# Skripsi_layout_v5.net
KiCad netlist of a schematic drawn in EAGLE
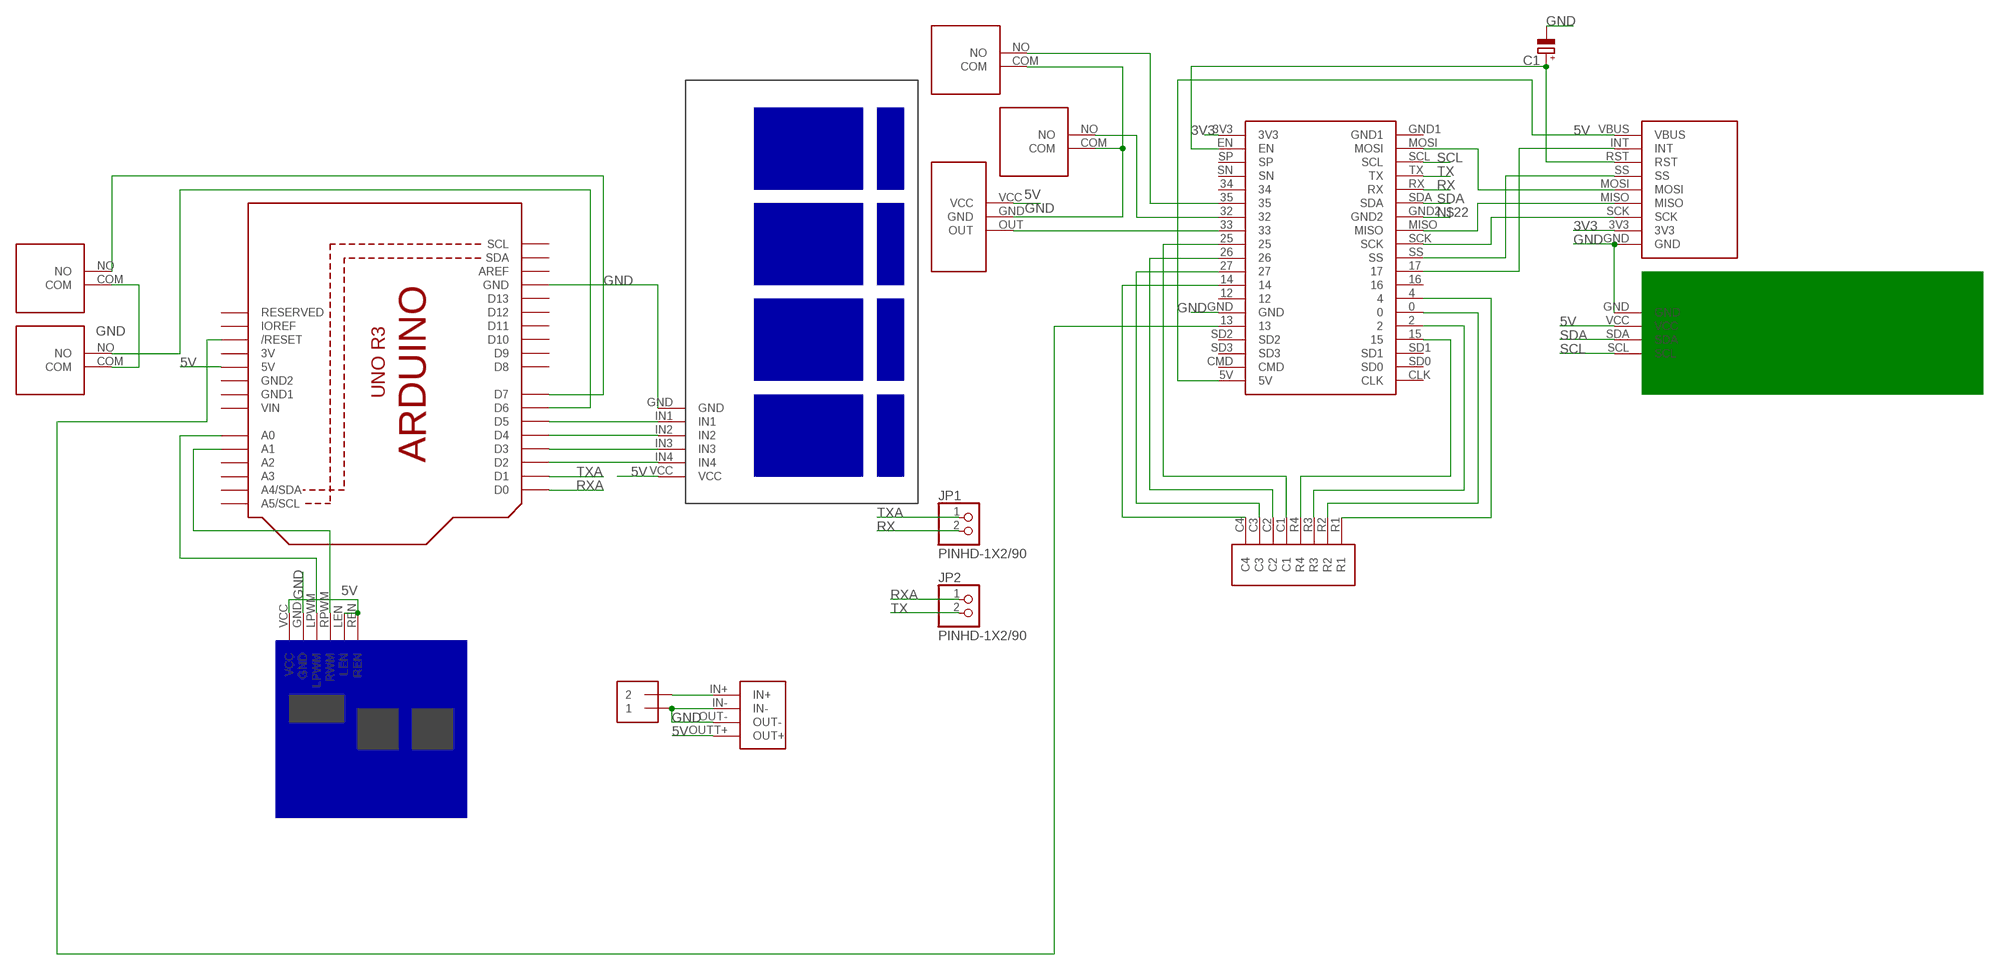
[diagram p0: schematic, sheet 1]

(export (version "E")
  (design (tool "Eeschema 10.0.6"))
  (components
    (comp (ref "C1")
      (value "C-POL_RADIAL-25MM-DIA")
      (footprint "eagle-import:CAPPRD550W110D1250H2500B")
      (libsource (lib "eagle-import") (part "C-POLRADIAL-25MM-DIA_"))
    )
    (comp (ref "J1")
      (value "1X2-3.5MM")
      (footprint "eagle-import:1X2-3.5MM")
      (libsource (lib "eagle-import") (part "1X2-3.5MM"))
    )
    (comp (ref "JP1")
      (value "PINHD-1X2/90")
      (footprint "eagle-import:1X02_90")
      (libsource (lib "eagle-import") (part "PINHD-1X2/90"))
    )
    (comp (ref "JP2")
      (value "PINHD-1X2/90")
      (footprint "eagle-import:1X02_90")
      (libsource (lib "eagle-import") (part "PINHD-1X2/90"))
    )
    (comp (ref "U$1")
      (value "ARDUINO_UNO")
      (footprint "eagle-import:ARDUINO_UNO")
      (libsource (lib "eagle-import") (part "ARDUINO_UNO"))
    )
    (comp (ref "U$2")
      (value "ESP32_NEW")
      (footprint "eagle-import:ESP32_NEW")
      (libsource (lib "eagle-import") (part "ESP32_NEW"))
    )
    (comp (ref "U$3")
      (value "USB_HOST")
      (footprint "eagle-import:USB_HOST")
      (libsource (lib "eagle-import") (part "USB_HOST"))
    )
    (comp (ref "U$4")
      (value "LCD_I2C")
      (footprint "eagle-import:LCD_I2C")
      (libsource (lib "eagle-import") (part "LCD_I2C"))
    )
    (comp (ref "U$5")
      (value "KEYPAD_4X4")
      (footprint "eagle-import:KEYPAD_4X4")
      (libsource (lib "eagle-import") (part "KEYPAD_4X4"))
    )
    (comp (ref "U$6")
      (value "IR_SENSOR")
      (footprint "eagle-import:IR_SENSOR")
      (libsource (lib "eagle-import") (part "IR_SENSOR"))
    )
    (comp (ref "U$7")
      (value "SWITCHLIMITER")
      (footprint "eagle-import:SWICHLIMITER")
      (libsource (lib "eagle-import") (part "SWITCHLIMITER"))
    )
    (comp (ref "U$8")
      (value "SWITCHLIMITER")
      (footprint "eagle-import:SWICHLIMITER")
      (libsource (lib "eagle-import") (part "SWITCHLIMITER"))
    )
    (comp (ref "U$9")
      (value "RELAY_4CHANNEL")
      (footprint "eagle-import:RELAY_4CHANNEL")
      (libsource (lib "eagle-import") (part "RELAY_4CHANNEL"))
    )
    (comp (ref "U$10")
      (value "MOTOR_DRIVER_BTS7960")
      (footprint "eagle-import:MOTOR_DRIVER_BTS7960")
      (libsource (lib "eagle-import") (part "MOTOR_DRIVER_BTS7960"))
    )
    (comp (ref "U$11")
      (value "SWITCHLIMITER")
      (footprint "eagle-import:SWICHLIMITER")
      (libsource (lib "eagle-import") (part "SWITCHLIMITER"))
    )
    (comp (ref "U$12")
      (value "SWITCHLIMITER")
      (footprint "eagle-import:SWICHLIMITER")
      (libsource (lib "eagle-import") (part "SWITCHLIMITER"))
    )
    (comp (ref "U$13")
      (value "XL4005E1")
      (footprint "eagle-import:XL4005E1")
      (libsource (lib "eagle-import") (part "XL4005E1"))
    )
  )
  (nets
    (net (code "1") (name "/3V") (class "Default")
      (node (ref "U$1") (pin "3V") (pinfunction "3V_3V") (pintype "power_in"))
    )
    (net (code "2") (name "/3V3") (class "Default")
      (node (ref "U$2") (pin "3V3") (pinfunction "3V3_3V3") (pintype "bidirectional"))
      (node (ref "U$3") (pin "3V3") (pinfunction "3V3_3V3") (pintype "bidirectional"))
    )
    (net (code "3") (name "/5V") (class "Default")
      (node (ref "U$1") (pin "5V") (pinfunction "5V_5V") (pintype "power_in"))
      (node (ref "U$10") (pin "LEN") (pinfunction "LEN_LEN") (pintype "bidirectional"))
      (node (ref "U$10") (pin "REN") (pinfunction "REN_REN") (pintype "bidirectional"))
      (node (ref "U$10") (pin "VCC") (pinfunction "VCC_VCC") (pintype "bidirectional"))
      (node (ref "U$13") (pin "OUTT+") (pinfunction "OUT+_OUTT+") (pintype "bidirectional"))
      (node (ref "U$2") (pin "5V") (pinfunction "5V_5V") (pintype "bidirectional"))
      (node (ref "U$3") (pin "VBUS") (pinfunction "VBUS_VBUS") (pintype "bidirectional"))
      (node (ref "U$4") (pin "VCC") (pinfunction "VCC_VCC") (pintype "bidirectional"))
      (node (ref "U$6") (pin "VCC") (pinfunction "VCC_VCC") (pintype "bidirectional"))
      (node (ref "U$9") (pin "VCC") (pinfunction "VCC_VCC") (pintype "bidirectional"))
    )
    (net (code "4") (name "/GND") (class "Default")
      (node (ref "C1") (pin "2") (pinfunction "-_2") (pintype "passive"))
      (node (ref "J1") (pin "1") (pinfunction "1_1") (pintype "passive"))
      (node (ref "U$1") (pin "GND") (pinfunction "GND_GND") (pintype "power_in"))
      (node (ref "U$10") (pin "GND") (pinfunction "GND_GND") (pintype "bidirectional"))
      (node (ref "U$11") (pin "COM") (pinfunction "COM_COM") (pintype "bidirectional"))
      (node (ref "U$12") (pin "COM") (pinfunction "COM_COM") (pintype "bidirectional"))
      (node (ref "U$13") (pin "IN-") (pinfunction "IN-_IN-") (pintype "bidirectional"))
      (node (ref "U$13") (pin "OUT-") (pinfunction "OUT-_OUT-") (pintype "bidirectional"))
      (node (ref "U$2") (pin "GND") (pinfunction "GND_GND") (pintype "bidirectional"))
      (node (ref "U$3") (pin "GND") (pinfunction "GND_GND") (pintype "bidirectional"))
      (node (ref "U$4") (pin "GND") (pinfunction "GND_GND") (pintype "bidirectional"))
      (node (ref "U$6") (pin "GND") (pinfunction "GND_GND") (pintype "bidirectional"))
      (node (ref "U$7") (pin "COM") (pinfunction "COM_COM") (pintype "bidirectional"))
      (node (ref "U$8") (pin "COM") (pinfunction "COM_COM") (pintype "bidirectional"))
      (node (ref "U$9") (pin "GND") (pinfunction "GND_GND") (pintype "bidirectional"))
    )
    (net (code "5") (name "/GND1") (class "Default")
      (node (ref "U$1") (pin "GND1") (pinfunction "GND1_GND1") (pintype "power_in"))
    )
    (net (code "6") (name "/GND2") (class "Default")
      (node (ref "U$1") (pin "GND2") (pinfunction "GND2_GND2") (pintype "power_in"))
    )
    (net (code "7") (name "/N$22") (class "Default")
      (node (ref "U$2") (pin "GND2") (pinfunction "GND2_GND2") (pintype "bidirectional"))
    )
    (net (code "8") (name "/RX") (class "Default")
      (node (ref "JP1") (pin "2") (pinfunction "2_2") (pintype "passive"))
      (node (ref "U$2") (pin "RX") (pinfunction "RX_RX") (pintype "bidirectional"))
    )
    (net (code "9") (name "/RXA") (class "Default")
      (node (ref "JP2") (pin "1") (pinfunction "1_1") (pintype "passive"))
      (node (ref "U$1") (pin "D0") (pinfunction "D0_D0") (pintype "bidirectional"))
    )
    (net (code "10") (name "/SCL") (class "Default")
      (node (ref "U$2") (pin "SCL") (pinfunction "SCL_SCL") (pintype "bidirectional"))
      (node (ref "U$4") (pin "SCL") (pinfunction "SCL_SCL") (pintype "bidirectional"))
    )
    (net (code "11") (name "/SDA") (class "Default")
      (node (ref "U$2") (pin "SDA") (pinfunction "SDA_SDA") (pintype "bidirectional"))
      (node (ref "U$4") (pin "SDA") (pinfunction "SDA_SDA") (pintype "bidirectional"))
    )
    (net (code "12") (name "/TX") (class "Default")
      (node (ref "JP2") (pin "2") (pinfunction "2_2") (pintype "passive"))
      (node (ref "U$2") (pin "TX") (pinfunction "TX_TX") (pintype "bidirectional"))
    )
    (net (code "13") (name "/TXA") (class "Default")
      (node (ref "JP1") (pin "1") (pinfunction "1_1") (pintype "passive"))
      (node (ref "U$1") (pin "D1") (pinfunction "D1_D1") (pintype "bidirectional"))
    )
    (net (code "14") (name "/VIN") (class "Default")
      (node (ref "U$1") (pin "VIN") (pinfunction "VIN_VIN") (pintype "power_in"))
    )
    (net (code "15") (name "Net-(C1-+)") (class "Default")
      (node (ref "C1") (pin "1") (pinfunction "+_1") (pintype "passive"))
      (node (ref "U$2") (pin "EN") (pinfunction "EN_EN") (pintype "bidirectional"))
      (node (ref "U$3") (pin "RST") (pinfunction "RST_RST") (pintype "bidirectional"))
    )
    (net (code "16") (name "Net-(J1-Pad2)") (class "Default")
      (node (ref "J1") (pin "2") (pinfunction "2_2") (pintype "passive"))
      (node (ref "U$13") (pin "IN+") (pinfunction "IN+_IN+") (pintype "bidirectional"))
    )
    (net (code "17") (name "Net-(U$1-PadA0)") (class "Default")
      (node (ref "U$1") (pin "A0") (pinfunction "A0_A0") (pintype "bidirectional"))
      (node (ref "U$10") (pin "LPWM") (pinfunction "LPWM_LPWM") (pintype "bidirectional"))
    )
    (net (code "18") (name "Net-(U$1-PadD2)") (class "Default")
      (node (ref "U$1") (pin "D2") (pinfunction "D2_D2") (pintype "bidirectional"))
      (node (ref "U$9") (pin "IN4") (pinfunction "IN4_IN4") (pintype "bidirectional"))
    )
    (net (code "19") (name "Net-(U$1-PadD3)") (class "Default")
      (node (ref "U$1") (pin "D3") (pinfunction "D3_D3") (pintype "bidirectional"))
      (node (ref "U$9") (pin "IN3") (pinfunction "IN3_IN3") (pintype "bidirectional"))
    )
    (net (code "20") (name "Net-(U$1-PadD4)") (class "Default")
      (node (ref "U$1") (pin "D4") (pinfunction "D4_D4") (pintype "bidirectional"))
      (node (ref "U$9") (pin "IN2") (pinfunction "IN2_IN2") (pintype "bidirectional"))
    )
    (net (code "21") (name "Net-(U$1-PadD5)") (class "Default")
      (node (ref "U$1") (pin "D5") (pinfunction "D5_D5") (pintype "bidirectional"))
      (node (ref "U$9") (pin "IN1") (pinfunction "IN1_IN1") (pintype "bidirectional"))
    )
    (net (code "22") (name "Net-(U$1-PadD6)") (class "Default")
      (node (ref "U$1") (pin "D6") (pinfunction "D6_D6") (pintype "bidirectional"))
      (node (ref "U$12") (pin "NO") (pinfunction "NO_NO") (pintype "bidirectional"))
    )
    (net (code "23") (name "Net-(U$1-PadD7)") (class "Default")
      (node (ref "U$1") (pin "D7") (pinfunction "D7_D7") (pintype "bidirectional"))
      (node (ref "U$11") (pin "NO") (pinfunction "NO_NO") (pintype "bidirectional"))
    )
    (net (code "24") (name "Net-(U$1-{slash}RESET)") (class "Default")
      (node (ref "U$1") (pin "RESET") (pinfunction "/RESET_RESET") (pintype "bidirectional"))
      (node (ref "U$2") (pin "13") (pinfunction "13_13") (pintype "bidirectional"))
    )
    (net (code "25") (name "Net-(U$2-Pad0)") (class "Default")
      (node (ref "U$2") (pin "0") (pinfunction "0_0") (pintype "bidirectional"))
      (node (ref "U$5") (pin "R2") (pinfunction "R2_R2") (pintype "bidirectional"))
    )
    (net (code "26") (name "Net-(U$2-Pad2)") (class "Default")
      (node (ref "U$2") (pin "2") (pinfunction "2_2") (pintype "bidirectional"))
      (node (ref "U$5") (pin "R3") (pinfunction "R3_R3") (pintype "bidirectional"))
    )
    (net (code "27") (name "Net-(U$2-Pad4)") (class "Default")
      (node (ref "U$2") (pin "4") (pinfunction "4_4") (pintype "bidirectional"))
      (node (ref "U$5") (pin "R1") (pinfunction "R1_R1") (pintype "bidirectional"))
    )
    (net (code "28") (name "Net-(U$2-Pad14)") (class "Default")
      (node (ref "U$2") (pin "14") (pinfunction "14_14") (pintype "bidirectional"))
      (node (ref "U$5") (pin "C4") (pinfunction "C4_C4") (pintype "bidirectional"))
    )
    (net (code "29") (name "Net-(U$2-Pad15)") (class "Default")
      (node (ref "U$2") (pin "15") (pinfunction "15_15") (pintype "bidirectional"))
      (node (ref "U$5") (pin "R4") (pinfunction "R4_R4") (pintype "bidirectional"))
    )
    (net (code "30") (name "Net-(U$2-Pad17)") (class "Default")
      (node (ref "U$2") (pin "17") (pinfunction "17_17") (pintype "bidirectional"))
      (node (ref "U$3") (pin "INT") (pinfunction "INT_INT") (pintype "bidirectional"))
    )
    (net (code "31") (name "Net-(U$2-Pad25)") (class "Default")
      (node (ref "U$2") (pin "25") (pinfunction "25_25") (pintype "bidirectional"))
      (node (ref "U$5") (pin "C1") (pinfunction "C1_C1") (pintype "bidirectional"))
    )
    (net (code "32") (name "Net-(U$2-Pad26)") (class "Default")
      (node (ref "U$2") (pin "26") (pinfunction "26_26") (pintype "bidirectional"))
      (node (ref "U$5") (pin "C2") (pinfunction "C2_C2") (pintype "bidirectional"))
    )
    (net (code "33") (name "Net-(U$2-Pad27)") (class "Default")
      (node (ref "U$2") (pin "27") (pinfunction "27_27") (pintype "bidirectional"))
      (node (ref "U$5") (pin "C3") (pinfunction "C3_C3") (pintype "bidirectional"))
    )
    (net (code "34") (name "Net-(U$2-Pad32)") (class "Default")
      (node (ref "U$2") (pin "32") (pinfunction "32_32") (pintype "bidirectional"))
      (node (ref "U$8") (pin "NO") (pinfunction "NO_NO") (pintype "bidirectional"))
    )
    (net (code "35") (name "Net-(U$2-Pad33)") (class "Default")
      (node (ref "U$2") (pin "33") (pinfunction "33_33") (pintype "bidirectional"))
      (node (ref "U$6") (pin "OUT") (pinfunction "OUT_OUT") (pintype "bidirectional"))
    )
    (net (code "36") (name "Net-(U$2-Pad35)") (class "Default")
      (node (ref "U$2") (pin "35") (pinfunction "35_35") (pintype "bidirectional"))
      (node (ref "U$7") (pin "NO") (pinfunction "NO_NO") (pintype "bidirectional"))
    )
    (net (code "37") (name "Net-(U$2-PadMISO)") (class "Default")
      (node (ref "U$2") (pin "MISO") (pinfunction "MISO_MISO") (pintype "bidirectional"))
      (node (ref "U$3") (pin "MISO") (pinfunction "MISO_MISO") (pintype "bidirectional"))
    )
    (net (code "38") (name "Net-(U$2-PadMOSI)") (class "Default")
      (node (ref "U$2") (pin "MOSI") (pinfunction "MOSI_MOSI") (pintype "bidirectional"))
      (node (ref "U$3") (pin "MOSI") (pinfunction "MOSI_MOSI") (pintype "bidirectional"))
    )
    (net (code "39") (name "Net-(U$2-PadSCK)") (class "Default")
      (node (ref "U$2") (pin "SCK") (pinfunction "SCK_SCK") (pintype "bidirectional"))
      (node (ref "U$3") (pin "SCK") (pinfunction "SCK_SCK") (pintype "bidirectional"))
    )
    (net (code "40") (name "Net-(U$2-PadSS)") (class "Default")
      (node (ref "U$2") (pin "SS") (pinfunction "SS_SS") (pintype "bidirectional"))
      (node (ref "U$3") (pin "SS") (pinfunction "SS_SS") (pintype "bidirectional"))
    )
    (net (code "41") (name "Net-(U$10-RWM)") (class "Default")
      (node (ref "U$1") (pin "A1") (pinfunction "A1_A1") (pintype "bidirectional"))
      (node (ref "U$10") (pin "RPWM") (pinfunction "RWM_RPWM") (pintype "bidirectional"))
    )
    (net (code "42") (name "unconnected-(U$1-A4{slash}SDA-PadA4)") (class "Default")
      (node (ref "U$1") (pin "A4") (pinfunction "A4/SDA_A4") (pintype "bidirectional"))
    )
    (net (code "43") (name "unconnected-(U$1-A5{slash}SCL-PadA5)") (class "Default")
      (node (ref "U$1") (pin "A5") (pinfunction "A5/SCL_A5") (pintype "bidirectional"))
    )
    (net (code "44") (name "unconnected-(U$1-PadA2)") (class "Default")
      (node (ref "U$1") (pin "A2") (pinfunction "A2_A2") (pintype "bidirectional"))
    )
    (net (code "45") (name "unconnected-(U$1-PadA3)") (class "Default")
      (node (ref "U$1") (pin "A3") (pinfunction "A3_A3") (pintype "bidirectional"))
    )
    (net (code "46") (name "unconnected-(U$1-PadAREF)") (class "Default")
      (node (ref "U$1") (pin "AREF") (pinfunction "AREF_AREF") (pintype "bidirectional"))
    )
    (net (code "47") (name "unconnected-(U$1-PadD8)") (class "Default")
      (node (ref "U$1") (pin "D8") (pinfunction "D8_D8") (pintype "bidirectional"))
    )
    (net (code "48") (name "unconnected-(U$1-PadD9)") (class "Default")
      (node (ref "U$1") (pin "D9") (pinfunction "D9_D9") (pintype "bidirectional"))
    )
    (net (code "49") (name "unconnected-(U$1-PadD10)") (class "Default")
      (node (ref "U$1") (pin "D10") (pinfunction "D10_D10") (pintype "bidirectional"))
    )
    (net (code "50") (name "unconnected-(U$1-PadD11)") (class "Default")
      (node (ref "U$1") (pin "D11") (pinfunction "D11_D11") (pintype "bidirectional"))
    )
    (net (code "51") (name "unconnected-(U$1-PadD12)") (class "Default")
      (node (ref "U$1") (pin "D12") (pinfunction "D12_D12") (pintype "bidirectional"))
    )
    (net (code "52") (name "unconnected-(U$1-PadD13)") (class "Default")
      (node (ref "U$1") (pin "D13") (pinfunction "D13_D13") (pintype "bidirectional"))
    )
    (net (code "53") (name "unconnected-(U$1-PadIOREF)") (class "Default")
      (node (ref "U$1") (pin "IOREF") (pinfunction "IOREF_IOREF") (pintype "output"))
    )
    (net (code "54") (name "unconnected-(U$1-PadRESERVED)") (class "Default")
      (node (ref "U$1") (pin "RESERVED") (pinfunction "RESERVED_RESERVED") (pintype "no_connect"))
    )
    (net (code "55") (name "unconnected-(U$1-PadSCL)") (class "Default")
      (node (ref "U$1") (pin "SCL") (pinfunction "SCL_SCL") (pintype "bidirectional"))
    )
    (net (code "56") (name "unconnected-(U$1-PadSDA)") (class "Default")
      (node (ref "U$1") (pin "SDA") (pinfunction "SDA_SDA") (pintype "bidirectional"))
    )
    (net (code "57") (name "unconnected-(U$2-Pad12)") (class "Default")
      (node (ref "U$2") (pin "12") (pinfunction "12_12") (pintype "bidirectional"))
    )
    (net (code "58") (name "unconnected-(U$2-Pad16)") (class "Default")
      (node (ref "U$2") (pin "16") (pinfunction "16_16") (pintype "bidirectional"))
    )
    (net (code "59") (name "unconnected-(U$2-Pad34)") (class "Default")
      (node (ref "U$2") (pin "34") (pinfunction "34_34") (pintype "bidirectional"))
    )
    (net (code "60") (name "unconnected-(U$2-PadCLK)") (class "Default")
      (node (ref "U$2") (pin "CLK") (pinfunction "CLK_CLK") (pintype "bidirectional"))
    )
    (net (code "61") (name "unconnected-(U$2-PadCMD)") (class "Default")
      (node (ref "U$2") (pin "CMD") (pinfunction "CMD_CMD") (pintype "bidirectional"))
    )
    (net (code "62") (name "unconnected-(U$2-PadGND1)") (class "Default")
      (node (ref "U$2") (pin "GND1") (pinfunction "GND1_GND1") (pintype "bidirectional"))
    )
    (net (code "63") (name "unconnected-(U$2-PadSD0)") (class "Default")
      (node (ref "U$2") (pin "SD0") (pinfunction "SD0_SD0") (pintype "bidirectional"))
    )
    (net (code "64") (name "unconnected-(U$2-PadSD1)") (class "Default")
      (node (ref "U$2") (pin "SD1") (pinfunction "SD1_SD1") (pintype "bidirectional"))
    )
    (net (code "65") (name "unconnected-(U$2-PadSD2)") (class "Default")
      (node (ref "U$2") (pin "SD2") (pinfunction "SD2_SD2") (pintype "bidirectional"))
    )
    (net (code "66") (name "unconnected-(U$2-PadSD3)") (class "Default")
      (node (ref "U$2") (pin "SD3") (pinfunction "SD3_SD3") (pintype "bidirectional"))
    )
    (net (code "67") (name "unconnected-(U$2-PadSN)") (class "Default")
      (node (ref "U$2") (pin "SN") (pinfunction "SN_SN") (pintype "bidirectional"))
    )
    (net (code "68") (name "unconnected-(U$2-PadSP)") (class "Default")
      (node (ref "U$2") (pin "SP") (pinfunction "SP_SP") (pintype "bidirectional"))
    )
  )
)
